# sbc-base.net
KiCad netlist of a schematic drawn in Altium Designer
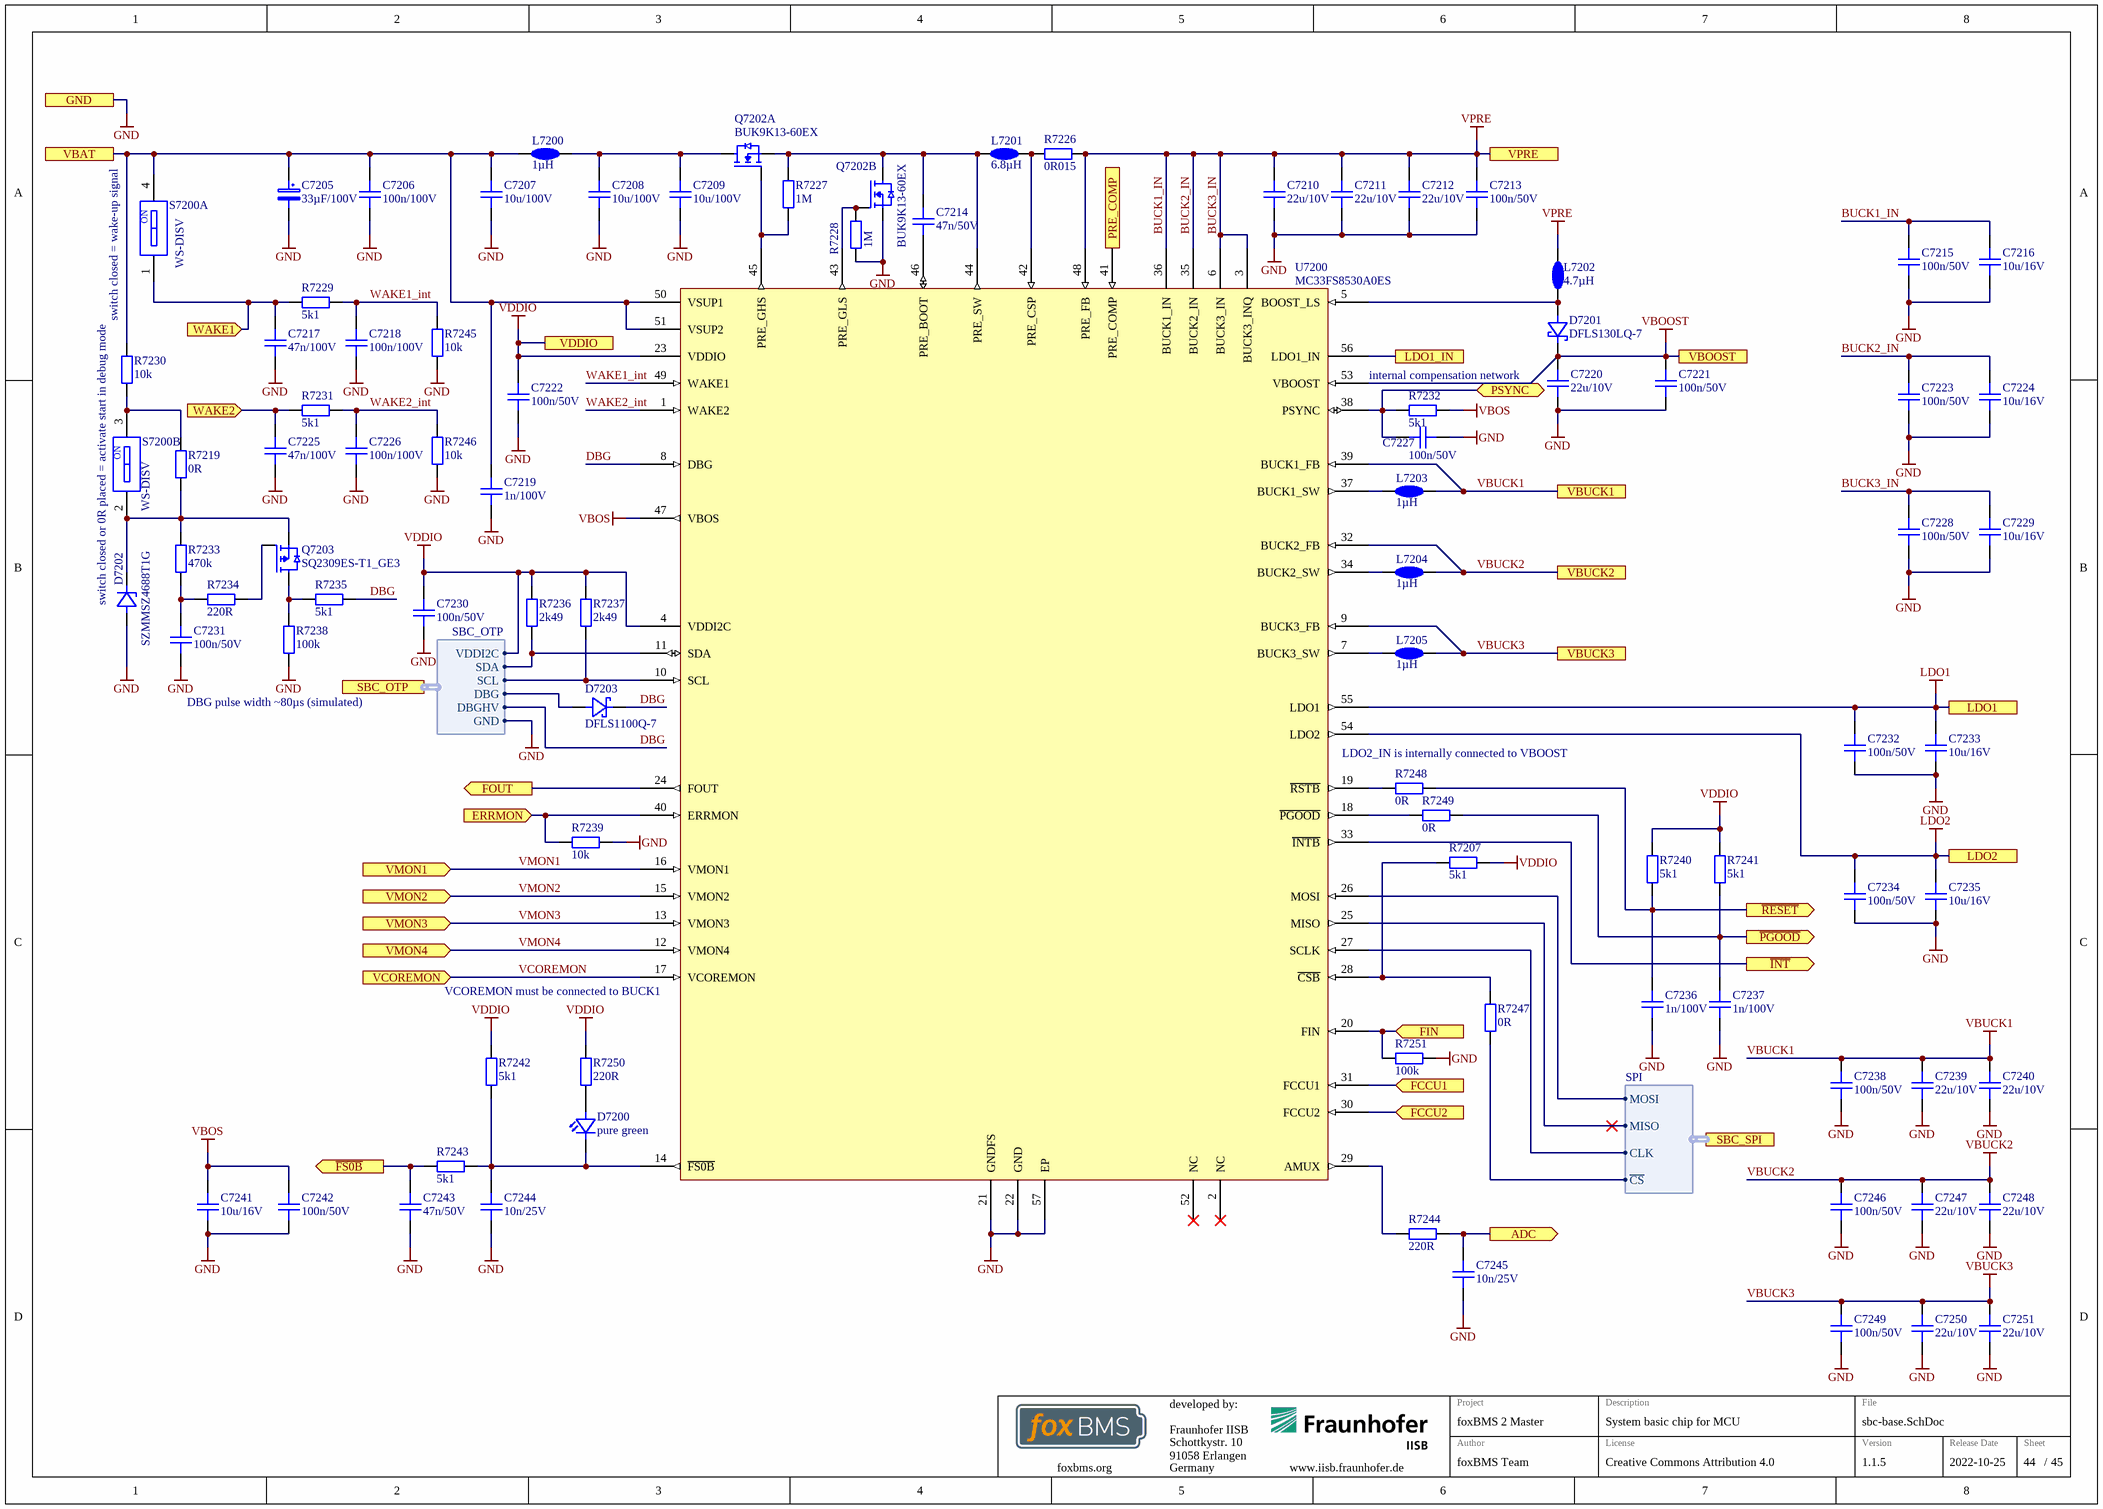
[diagram p0: sbc-base.SchDoc]

(export (version "E")
  (design (tool "Eeschema 10.0.6"))
  (components
    (comp (ref "C7205")
      (value "33µF/100V")
      (footprint "ELECTROLYTIC_CAP_PANASONIC_G")
      (description "SMD Electrolytic Capacitor")
      (fields (field (name "PART NUMBER") "EEE-TG2A330P") (field (name "TOLERANCE") "+-20%"))
      (libsource (lib "OE750") (part "C_Pol"))
    )
    (comp (ref "C7206")
      (value "100n/100V")
      (footprint "CAPC1608X08N")
      (description "MLCC")
      (fields (field (name "PART NUMBER") "gen_C_ceramic_100n_100V_X7R_0603"))
      (libsource (lib "OE750") (part "C"))
    )
    (comp (ref "C7207")
      (value "10u/100V")
      (footprint "CAPC5750X28N")
      (description "MLCC")
      (fields (field (name "PART NUMBER") "gen_C_ceramic_10u_100V_X7S_2220"))
      (libsource (lib "OE750") (part "C"))
    )
    (comp (ref "C7208")
      (value "10u/100V")
      (footprint "CAPC5750X28N")
      (description "MLCC")
      (fields (field (name "PART NUMBER") "gen_C_ceramic_10u_100V_X7S_2220"))
      (libsource (lib "OE750") (part "C"))
    )
    (comp (ref "C7209")
      (value "10u/100V")
      (footprint "CAPC5750X28N")
      (description "MLCC")
      (fields (field (name "PART NUMBER") "gen_C_ceramic_10u_100V_X7S_2220"))
      (libsource (lib "OE750") (part "C"))
    )
    (comp (ref "C7210")
      (value "22u/10V")
      (footprint "CAPC3216X18N")
      (description "MLCC")
      (fields (field (name "PART NUMBER") "gen_C_ceramic_22u_10V_X7R_1206"))
      (libsource (lib "OE750") (part "C"))
    )
    (comp (ref "C7211")
      (value "22u/10V")
      (footprint "CAPC3216X18N")
      (description "MLCC")
      (fields (field (name "PART NUMBER") "gen_C_ceramic_22u_10V_X7R_1206"))
      (libsource (lib "OE750") (part "C"))
    )
    (comp (ref "C7212")
      (value "22u/10V")
      (footprint "CAPC3216X18N")
      (description "MLCC")
      (fields (field (name "PART NUMBER") "gen_C_ceramic_22u_10V_X7R_1206"))
      (libsource (lib "OE750") (part "C"))
    )
    (comp (ref "C7213")
      (value "100n/50V")
      (footprint "CAPC1005X06N")
      (description "MLCC")
      (fields (field (name "PART NUMBER") "gen_C_ceramic_100n_50V_X7R_0402"))
      (libsource (lib "OE750") (part "C"))
    )
    (comp (ref "C7214")
      (value "47n/50V")
      (footprint "CAPC1005X06N")
      (description "MLCC")
      (fields (field (name "PART NUMBER") "gen_C_ceramic_47n_50V_X7R_0402"))
      (libsource (lib "OE750") (part "C"))
    )
    (comp (ref "C7215")
      (value "100n/50V")
      (footprint "CAPC1005X06N")
      (description "MLCC")
      (fields (field (name "PART NUMBER") "gen_C_ceramic_100n_50V_X7R_0402"))
      (libsource (lib "OE750") (part "C"))
    )
    (comp (ref "C7216")
      (value "10u/16V")
      (footprint "CAPC2012X14N")
      (description "MLCC")
      (fields (field (name "PART NUMBER") "gen_C_ceramic_10u_16V_X7R_0805"))
      (libsource (lib "OE750") (part "C"))
    )
    (comp (ref "C7217")
      (value "47n/100V")
      (footprint "CAPC1608X08N")
      (description "MLCC")
      (fields (field (name "PART NUMBER") "gen_C_ceramic_47n_100V_X7R_0603"))
      (libsource (lib "OE750") (part "C"))
    )
    (comp (ref "C7218")
      (value "100n/100V")
      (footprint "CAPC1608X08N")
      (description "MLCC")
      (fields (field (name "PART NUMBER") "gen_C_ceramic_100n_100V_X7R_0603"))
      (libsource (lib "OE750") (part "C"))
    )
    (comp (ref "C7219")
      (value "1n/100V")
      (footprint "CAPC1005X06N")
      (description "MLCC")
      (fields (field (name "PART NUMBER") "gen_C_ceramic_1n_100V_X7R_0402"))
      (libsource (lib "OE750") (part "C"))
    )
    (comp (ref "C7220")
      (value "22u/10V")
      (footprint "CAPC3216X18N")
      (description "MLCC")
      (fields (field (name "PART NUMBER") "gen_C_ceramic_22u_10V_X7R_1206"))
      (libsource (lib "OE750") (part "C"))
    )
    (comp (ref "C7221")
      (value "100n/50V")
      (footprint "CAPC1005X06N")
      (description "MLCC")
      (fields (field (name "PART NUMBER") "gen_C_ceramic_100n_50V_X7R_0402"))
      (libsource (lib "OE750") (part "C"))
    )
    (comp (ref "C7222")
      (value "100n/50V")
      (footprint "CAPC1005X06N")
      (description "MLCC")
      (fields (field (name "PART NUMBER") "gen_C_ceramic_100n_50V_X7R_0402"))
      (libsource (lib "OE750") (part "C"))
    )
    (comp (ref "C7223")
      (value "100n/50V")
      (footprint "CAPC1005X06N")
      (description "MLCC")
      (fields (field (name "PART NUMBER") "gen_C_ceramic_100n_50V_X7R_0402"))
      (libsource (lib "OE750") (part "C"))
    )
    (comp (ref "C7224")
      (value "10u/16V")
      (footprint "CAPC2012X14N")
      (description "MLCC")
      (fields (field (name "PART NUMBER") "gen_C_ceramic_10u_16V_X7R_0805"))
      (libsource (lib "OE750") (part "C"))
    )
    (comp (ref "C7225")
      (value "47n/100V")
      (footprint "CAPC1608X08N")
      (description "MLCC")
      (fields (field (name "PART NUMBER") "gen_C_ceramic_47n_100V_X7R_0603"))
      (libsource (lib "OE750") (part "C"))
    )
    (comp (ref "C7226")
      (value "100n/100V")
      (footprint "CAPC1608X08N")
      (description "MLCC")
      (fields (field (name "PART NUMBER") "gen_C_ceramic_100n_100V_X7R_0603"))
      (libsource (lib "OE750") (part "C"))
    )
    (comp (ref "C7227")
      (value "100n/50V")
      (footprint "CAPC1005X06N")
      (description "MLCC")
      (fields (field (name "PART NUMBER") "gen_C_ceramic_100n_50V_X7R_0402"))
      (libsource (lib "OE750") (part "C"))
    )
    (comp (ref "C7228")
      (value "100n/50V")
      (footprint "CAPC1005X06N")
      (description "MLCC")
      (fields (field (name "PART NUMBER") "gen_C_ceramic_100n_50V_X7R_0402"))
      (libsource (lib "OE750") (part "C"))
    )
    (comp (ref "C7229")
      (value "10u/16V")
      (footprint "CAPC2012X14N")
      (description "MLCC")
      (fields (field (name "PART NUMBER") "gen_C_ceramic_10u_16V_X7R_0805"))
      (libsource (lib "OE750") (part "C"))
    )
    (comp (ref "C7230")
      (value "100n/50V")
      (footprint "CAPC1005X06N")
      (description "MLCC")
      (fields (field (name "PART NUMBER") "gen_C_ceramic_100n_50V_X7R_0402"))
      (libsource (lib "OE750") (part "C"))
    )
    (comp (ref "C7231")
      (value "100n/50V")
      (footprint "CAPC1005X06N")
      (description "MLCC")
      (fields (field (name "PART NUMBER") "gen_C_ceramic_100n_50V_X7R_0402"))
      (libsource (lib "OE750") (part "C"))
    )
    (comp (ref "C7232")
      (value "100n/50V")
      (footprint "CAPC1005X06N")
      (description "MLCC")
      (fields (field (name "PART NUMBER") "gen_C_ceramic_100n_50V_X7R_0402"))
      (libsource (lib "OE750") (part "C"))
    )
    (comp (ref "C7233")
      (value "10u/16V")
      (footprint "CAPC2012X14N")
      (description "MLCC")
      (fields (field (name "PART NUMBER") "gen_C_ceramic_10u_16V_X7R_0805"))
      (libsource (lib "OE750") (part "C"))
    )
    (comp (ref "C7234")
      (value "100n/50V")
      (footprint "CAPC1005X06N")
      (description "MLCC")
      (fields (field (name "PART NUMBER") "gen_C_ceramic_100n_50V_X7R_0402"))
      (libsource (lib "OE750") (part "C"))
    )
    (comp (ref "C7235")
      (value "10u/16V")
      (footprint "CAPC2012X14N")
      (description "MLCC")
      (fields (field (name "PART NUMBER") "gen_C_ceramic_10u_16V_X7R_0805"))
      (libsource (lib "OE750") (part "C"))
    )
    (comp (ref "C7236")
      (value "1n/100V")
      (footprint "CAPC1005X06N")
      (description "MLCC")
      (fields (field (name "PART NUMBER") "gen_C_ceramic_1n_100V_X7R_0402"))
      (libsource (lib "OE750") (part "C"))
    )
    (comp (ref "C7237")
      (value "1n/100V")
      (footprint "CAPC1005X06N")
      (description "MLCC")
      (fields (field (name "PART NUMBER") "gen_C_ceramic_1n_100V_X7R_0402"))
      (libsource (lib "OE750") (part "C"))
    )
    (comp (ref "C7238")
      (value "100n/50V")
      (footprint "CAPC1005X06N")
      (description "MLCC")
      (fields (field (name "PART NUMBER") "gen_C_ceramic_100n_50V_X7R_0402"))
      (libsource (lib "OE750") (part "C"))
    )
    (comp (ref "C7239")
      (value "22u/10V")
      (footprint "CAPC3216X18N")
      (description "MLCC")
      (fields (field (name "PART NUMBER") "gen_C_ceramic_22u_10V_X7R_1206"))
      (libsource (lib "OE750") (part "C"))
    )
    (comp (ref "C7240")
      (value "22u/10V")
      (footprint "CAPC3216X18N")
      (description "MLCC")
      (fields (field (name "PART NUMBER") "gen_C_ceramic_22u_10V_X7R_1206"))
      (libsource (lib "OE750") (part "C"))
    )
    (comp (ref "C7241")
      (value "10u/16V")
      (footprint "CAPC2012X14N")
      (description "MLCC")
      (fields (field (name "PART NUMBER") "gen_C_ceramic_10u_16V_X7R_0805"))
      (libsource (lib "OE750") (part "C"))
    )
    (comp (ref "C7242")
      (value "100n/50V")
      (footprint "CAPC1005X06N")
      (description "MLCC")
      (fields (field (name "PART NUMBER") "gen_C_ceramic_100n_50V_X7R_0402"))
      (libsource (lib "OE750") (part "C"))
    )
    (comp (ref "C7243")
      (value "47n/50V")
      (footprint "CAPC1005X06N")
      (description "MLCC")
      (fields (field (name "PART NUMBER") "gen_C_ceramic_47n_50V_X7R_0402"))
      (libsource (lib "OE750") (part "C"))
    )
    (comp (ref "C7244")
      (value "10n/25V")
      (footprint "CAPC1005X06N")
      (description "MLCC")
      (fields (field (name "PART NUMBER") "gen_C_ceramic_10n_25V_X7R_0402"))
      (libsource (lib "OE750") (part "C"))
    )
    (comp (ref "C7245")
      (value "10n/25V")
      (footprint "CAPC1005X06N")
      (description "MLCC")
      (fields (field (name "PART NUMBER") "gen_C_ceramic_10n_25V_X7R_0402"))
      (libsource (lib "OE750") (part "C"))
    )
    (comp (ref "C7246")
      (value "100n/50V")
      (footprint "CAPC1005X06N")
      (description "MLCC")
      (fields (field (name "PART NUMBER") "gen_C_ceramic_100n_50V_X7R_0402"))
      (libsource (lib "OE750") (part "C"))
    )
    (comp (ref "C7247")
      (value "22u/10V")
      (footprint "CAPC3216X18N")
      (description "MLCC")
      (fields (field (name "PART NUMBER") "gen_C_ceramic_22u_10V_X7R_1206"))
      (libsource (lib "OE750") (part "C"))
    )
    (comp (ref "C7248")
      (value "22u/10V")
      (footprint "CAPC3216X18N")
      (description "MLCC")
      (fields (field (name "PART NUMBER") "gen_C_ceramic_22u_10V_X7R_1206"))
      (libsource (lib "OE750") (part "C"))
    )
    (comp (ref "C7249")
      (value "100n/50V")
      (footprint "CAPC1005X06N")
      (description "MLCC")
      (fields (field (name "PART NUMBER") "gen_C_ceramic_100n_50V_X7R_0402"))
      (libsource (lib "OE750") (part "C"))
    )
    (comp (ref "C7250")
      (value "22u/10V")
      (footprint "CAPC3216X18N")
      (description "MLCC")
      (fields (field (name "PART NUMBER") "gen_C_ceramic_22u_10V_X7R_1206"))
      (libsource (lib "OE750") (part "C"))
    )
    (comp (ref "C7251")
      (value "22u/10V")
      (footprint "CAPC3216X18N")
      (description "MLCC")
      (fields (field (name "PART NUMBER") "gen_C_ceramic_22u_10V_X7R_1206"))
      (libsource (lib "OE750") (part "C"))
    )
    (comp (ref "D7200")
      (value "pure green")
      (footprint "LEDC1608X07N")
      (description "TLMP1100-GS08")
      (fields (field (name "PART NUMBER") "LED_0603_pure_green_AECQ") (field (name "MANUFACTURER") "Vishay"))
      (libsource (lib "OE750") (part "D_LED"))
    )
    (comp (ref "D7201")
      (value "DFLS130LQ-7")
      (footprint "PowerDI123")
      (description "Schottky Diode")
      (fields (field (name "MANUFACTURER") "Diodes Inc."))
      (libsource (lib "OE750") (part "D_Schottky"))
    )
    (comp (ref "D7202")
      (value "SZMMSZ4688T1G")
      (footprint "SOD-123_CASE-425-04-ISSUE-G")
      (description "Zener Diode")
      (fields (field (name "MANUFACTURER") "ON Semiconductor"))
      (libsource (lib "OE750") (part "D_Zener"))
    )
    (comp (ref "D7203")
      (value "DFLS1100Q-7")
      (footprint "PowerDI123")
      (description "Schottky Diode")
      (fields (field (name "MANUFACTURER") "Diodes Inc."))
      (libsource (lib "OE750") (part "D_Schottky"))
    )
    (comp (ref "L7200")
      (value "1µH")
      (footprint "ASPIAIG-S4035")
      (description "Power Inductor")
      (fields (field (name "PART NUMBER") "ASPIAIG-S4035-1R0M-T") (field (name "MANUFACTURER") "Abracon LLC"))
      (libsource (lib "OE750") (part "L"))
    )
    (comp (ref "L7201")
      (value "6.8µH")
      (footprint "PA4342.XXXNLT_Footprint_2")
      (description "Power Inductor")
      (fields (field (name "PART NUMBER") "PA4342.682NLT") (field (name "MANUFACTURER") "Pulse"))
      (libsource (lib "OE750") (part "L"))
    )
    (comp (ref "L7202")
      (value "4.7µH")
      (footprint "ASPIAIG-S4035")
      (description "Power Inductor")
      (fields (field (name "PART NUMBER") "ASPIAIG-S4035-4R7M-T") (field (name "MANUFACTURER") "Abracon LLC"))
      (libsource (lib "OE750") (part "L"))
    )
    (comp (ref "L7203")
      (value "1µH")
      (footprint "TDK_TFM252012")
      (description "Power Inductor")
      (fields (field (name "PART NUMBER") "TFM252012ALMA1R0MTAA") (field (name "MANUFACTURER") "TDK"))
      (libsource (lib "OE750") (part "L"))
    )
    (comp (ref "L7204")
      (value "1µH")
      (footprint "TDK_TFM252012")
      (description "Power Inductor")
      (fields (field (name "PART NUMBER") "TFM252012ALMA1R0MTAA") (field (name "MANUFACTURER") "TDK"))
      (libsource (lib "OE750") (part "L"))
    )
    (comp (ref "L7205")
      (value "1µH")
      (footprint "TDK_TFM252012")
      (description "Power Inductor")
      (fields (field (name "PART NUMBER") "TFM252012ALMA1R0MTAA") (field (name "MANUFACTURER") "TDK"))
      (libsource (lib "OE750") (part "L"))
    )
    (comp (ref "Q7202")
      (value "BUK9K13-60EX")
      (footprint "NXP-SOT1205_N")
      (description "Dual N-channel 60 V, 12.5 mΩ logic level MOSFET")
      (fields (field (name "MANUFACTURER") "Nexperia"))
      (libsource (lib "OE750") (part "BUK9K35-60E"))
    )
    (comp (ref "Q7203")
      (value "SQ2309ES-T1_GE3")
      (footprint "SOT95P237X110-3N")
      (description "MOSFET-Transistor, p-channel, -1.7 A, -60 V")
      (fields (field (name "MANUFACTURER") "Vishay"))
      (libsource (lib "OE750") (part "PMOS"))
    )
    (comp (ref "R7207")
      (value "5k1")
      (footprint "RESC1005X04N")
      (description "SMD Resistor 5k1 0402")
      (fields (field (name "PART NUMBER") "gen_R_5k1_0402") (field (name "TOLERANCE") "1%"))
      (libsource (lib "OE750") (part "R"))
    )
    (comp (ref "R7219")
      (value "0R")
      (footprint "RESC1005X04N")
      (description "SMD Resistor 0R 0402")
      (fields (field (name "PART NUMBER") "gen_R_0R_0402") (field (name "POWER") "0.063W"))
      (libsource (lib "OE750") (part "R"))
    )
    (comp (ref "R7226")
      (value "0R015")
      (footprint "PANASONIC_ERJ-B1")
      (description "SMD Shunt Resistor 0R015")
      (fields (field (name "PART NUMBER") "ERJ-B1CFR015U") (field (name "TOLERANCE") "1%"))
      (libsource (lib "OE750") (part "R"))
    )
    (comp (ref "R7227")
      (value "1M")
      (footprint "RESC1005X04N")
      (description "SMD Resistor 1M 0402")
      (fields (field (name "PART NUMBER") "gen_R_1M_0402") (field (name "TOLERANCE") "1%"))
      (libsource (lib "OE750") (part "R"))
    )
    (comp (ref "R7228")
      (value "1M")
      (footprint "RESC1005X04N")
      (description "SMD Resistor 1M 0402")
      (fields (field (name "PART NUMBER") "gen_R_1M_0402") (field (name "TOLERANCE") "1%"))
      (libsource (lib "OE750") (part "R"))
    )
    (comp (ref "R7229")
      (value "5k1")
      (footprint "RESC1005X04N")
      (description "SMD Resistor 5k1 0402")
      (fields (field (name "PART NUMBER") "gen_R_5k1_0402") (field (name "TOLERANCE") "1%"))
      (libsource (lib "OE750") (part "R"))
    )
    (comp (ref "R7230")
      (value "10k")
      (footprint "RESC1005X04N")
      (description "SMD Resistor 10k 0402")
      (fields (field (name "PART NUMBER") "gen_R_10k_0402") (field (name "TOLERANCE") "1%"))
      (libsource (lib "OE750") (part "R"))
    )
    (comp (ref "R7231")
      (value "5k1")
      (footprint "RESC1005X04N")
      (description "SMD Resistor 5k1 0402")
      (fields (field (name "PART NUMBER") "gen_R_5k1_0402") (field (name "TOLERANCE") "1%"))
      (libsource (lib "OE750") (part "R"))
    )
    (comp (ref "R7232")
      (value "5k1")
      (footprint "RESC1005X04N")
      (description "SMD Resistor 5k1 0402")
      (fields (field (name "PART NUMBER") "gen_R_5k1_0402") (field (name "TOLERANCE") "1%"))
      (libsource (lib "OE750") (part "R"))
    )
    (comp (ref "R7233")
      (value "470k")
      (footprint "RESC1005X04N")
      (description "SMD Resistor 470k 0402")
      (fields (field (name "PART NUMBER") "gen_R_470k_0402") (field (name "TOLERANCE") "1%"))
      (libsource (lib "OE750") (part "R"))
    )
    (comp (ref "R7234")
      (value "220R")
      (footprint "RESC1005X04N")
      (description "SMD Resistor 220R 0402")
      (fields (field (name "PART NUMBER") "gen_R_220R_0402") (field (name "TOLERANCE") "1%"))
      (libsource (lib "OE750") (part "R"))
    )
    (comp (ref "R7235")
      (value "5k1")
      (footprint "RESC1005X04N")
      (description "SMD Resistor 5k1 0402")
      (fields (field (name "PART NUMBER") "gen_R_5k1_0402") (field (name "TOLERANCE") "1%"))
      (libsource (lib "OE750") (part "R"))
    )
    (comp (ref "R7236")
      (value "2k49")
      (footprint "RESC1005X04N")
      (description "SMD Resistor 2k49 0402")
      (fields (field (name "PART NUMBER") "gen_R_2k49_0402") (field (name "TOLERANCE") "1%"))
      (libsource (lib "OE750") (part "R"))
    )
    (comp (ref "R7237")
      (value "2k49")
      (footprint "RESC1005X04N")
      (description "SMD Resistor 2k49 0402")
      (fields (field (name "PART NUMBER") "gen_R_2k49_0402") (field (name "TOLERANCE") "1%"))
      (libsource (lib "OE750") (part "R"))
    )
    (comp (ref "R7238")
      (value "100k")
      (footprint "RESC1005X04N")
      (description "SMD Resistor 100k 0402")
      (fields (field (name "PART NUMBER") "gen_R_100k_0402") (field (name "TOLERANCE") "1%"))
      (libsource (lib "OE750") (part "R"))
    )
    (comp (ref "R7239")
      (value "10k")
      (footprint "RESC1005X04N")
      (description "SMD Resistor 10k 0402")
      (fields (field (name "PART NUMBER") "gen_R_10k_0402") (field (name "TOLERANCE") "1%"))
      (libsource (lib "OE750") (part "R"))
    )
    (comp (ref "R7240")
      (value "5k1")
      (footprint "RESC1005X04N")
      (description "SMD Resistor 5k1 0402")
      (fields (field (name "PART NUMBER") "gen_R_5k1_0402") (field (name "TOLERANCE") "1%"))
      (libsource (lib "OE750") (part "R"))
    )
    (comp (ref "R7241")
      (value "5k1")
      (footprint "RESC1005X04N")
      (description "SMD Resistor 5k1 0402")
      (fields (field (name "PART NUMBER") "gen_R_5k1_0402") (field (name "TOLERANCE") "1%"))
      (libsource (lib "OE750") (part "R"))
    )
    (comp (ref "R7242")
      (value "5k1")
      (footprint "RESC1005X04N")
      (description "SMD Resistor 5k1 0402")
      (fields (field (name "PART NUMBER") "gen_R_5k1_0402") (field (name "TOLERANCE") "1%"))
      (libsource (lib "OE750") (part "R"))
    )
    (comp (ref "R7243")
      (value "5k1")
      (footprint "RESC1005X04N")
      (description "SMD Resistor 5k1 0402")
      (fields (field (name "PART NUMBER") "gen_R_5k1_0402") (field (name "TOLERANCE") "1%"))
      (libsource (lib "OE750") (part "R"))
    )
    (comp (ref "R7244")
      (value "220R")
      (footprint "RESC1005X04N")
      (description "SMD Resistor 220R 0402")
      (fields (field (name "PART NUMBER") "gen_R_220R_0402") (field (name "TOLERANCE") "1%"))
      (libsource (lib "OE750") (part "R"))
    )
    (comp (ref "R7245")
      (value "10k")
      (footprint "RESC1005X04N")
      (description "SMD Resistor 10k 0402")
      (fields (field (name "PART NUMBER") "gen_R_10k_0402") (field (name "TOLERANCE") "1%"))
      (libsource (lib "OE750") (part "R"))
    )
    (comp (ref "R7246")
      (value "10k")
      (footprint "RESC1005X04N")
      (description "SMD Resistor 10k 0402")
      (fields (field (name "PART NUMBER") "gen_R_10k_0402") (field (name "TOLERANCE") "1%"))
      (libsource (lib "OE750") (part "R"))
    )
    (comp (ref "R7247")
      (value "0R")
      (footprint "RESC1005X04N")
      (description "SMD Resistor 0R 0402")
      (fields (field (name "PART NUMBER") "gen_R_0R_0402") (field (name "POWER") "0.063W"))
      (libsource (lib "OE750") (part "R"))
    )
    (comp (ref "R7248")
      (value "0R")
      (footprint "RESC1005X04N")
      (description "SMD Resistor 0R 0402")
      (fields (field (name "PART NUMBER") "gen_R_0R_0402") (field (name "POWER") "0.063W"))
      (libsource (lib "OE750") (part "R"))
    )
    (comp (ref "R7249")
      (value "0R")
      (footprint "RESC1005X04N")
      (description "SMD Resistor 0R 0402")
      (fields (field (name "PART NUMBER") "gen_R_0R_0402") (field (name "POWER") "0.063W"))
      (libsource (lib "OE750") (part "R"))
    )
    (comp (ref "R7250")
      (value "220R")
      (footprint "RESC1005X04N")
      (description "SMD Resistor 220R 0402")
      (fields (field (name "PART NUMBER") "gen_R_220R_0402") (field (name "TOLERANCE") "1%"))
      (libsource (lib "OE750") (part "R"))
    )
    (comp (ref "R7251")
      (value "100k")
      (footprint "RESC1005X04N")
      (description "SMD Resistor 100k 0402")
      (fields (field (name "PART NUMBER") "gen_R_100k_0402") (field (name "TOLERANCE") "1%"))
      (libsource (lib "OE750") (part "R"))
    )
    (comp (ref "S7200")
      (value "WS-DISV")
      (footprint "WE_416131160802")
      (description "WS-DISV Small Compact SMT DipSwitch")
      (fields (field (name "PART NUMBER") "WE_416131160802") (field (name "MANUFACTURER") "Würth Elektronik"))
      (libsource (lib "OE750") (part "WE_416131160802"))
    )
    (comp (ref "U7200")
      (value "MC33FS8530A0ES")
      (footprint "MC33FS8530A0ES")
      (description "Fail-safe system basis chip with multiple SMPS and LDO")
      (fields (field (name "MANUFACTURER") "NXP"))
      (libsource (lib "OE750") (part "MC33FS8530A0ES"))
    )
  )
  (nets
    (net (code "3") (name "/ADC") (class "Default")
      (node (ref "C7245") (pin "2") (pinfunction "2_2") (pintype "passive"))
      (node (ref "R7244") (pin "2") (pinfunction "2_2") (pintype "passive"))
    )
    (net (code "4") (name "/CLK") (class "Default")
      (node (ref "U7200") (pin "27") (pinfunction "SCLK_27") (pintype "input"))
    )
    (net (code "5") (name "/DBG") (class "Default")
      (node (ref "D7203") (pin "1") (pinfunction "K_1") (pintype "passive"))
      (node (ref "R7235") (pin "1") (pinfunction "1_1") (pintype "passive"))
      (node (ref "U7200") (pin "8") (pinfunction "DBG_8") (pintype "input"))
    )
    (net (code "6") (name "/ERRMON") (class "Default")
      (node (ref "R7239") (pin "2") (pinfunction "2_2") (pintype "passive"))
      (node (ref "U7200") (pin "40") (pinfunction "ERRMON_40") (pintype "input"))
    )
    (net (code "7") (name "/FCCU1") (class "Default")
      (node (ref "U7200") (pin "31") (pinfunction "FCCU1_31") (pintype "input"))
    )
    (net (code "8") (name "/FCCU2") (class "Default")
      (node (ref "U7200") (pin "30") (pinfunction "FCCU2_30") (pintype "input"))
    )
    (net (code "9") (name "/FIN") (class "Default")
      (node (ref "R7251") (pin "1") (pinfunction "1_1") (pintype "passive"))
      (node (ref "U7200") (pin "20") (pinfunction "FIN_20") (pintype "input"))
    )
    (net (code "10") (name "/FOUT") (class "Default")
      (node (ref "U7200") (pin "24") (pinfunction "FOUT_24") (pintype "output"))
    )
    (net (code "11") (name "/FS0B") (class "Default")
      (node (ref "C7243") (pin "2") (pinfunction "2_2") (pintype "passive"))
      (node (ref "R7243") (pin "2") (pinfunction "2_2") (pintype "passive"))
    )
    (net (code "12") (name "/INT") (class "Default")
      (node (ref "U7200") (pin "33") (pinfunction "INTB_33") (pintype "output"))
    )
    (net (code "13") (name "/LDO1_IN") (class "Default")
      (node (ref "U7200") (pin "56") (pinfunction "LDO1_IN_56") (pintype "power_in"))
    )
    (net (code "14") (name "/MISO") (class "Default")
      (node (ref "U7200") (pin "25") (pinfunction "MISO_25") (pintype "output"))
    )
    (net (code "15") (name "/MOSI") (class "Default")
      (node (ref "U7200") (pin "26") (pinfunction "MOSI_26") (pintype "input"))
    )
    (net (code "16") (name "/PGOOD") (class "Default")
      (node (ref "C7237") (pin "2") (pinfunction "2_2") (pintype "passive"))
      (node (ref "R7241") (pin "1") (pinfunction "1_1") (pintype "passive"))
      (node (ref "R7249") (pin "2") (pinfunction "2_2") (pintype "passive"))
    )
    (net (code "17") (name "/PRE_COMP") (class "Default")
      (node (ref "U7200") (pin "41") (pinfunction "PRE_COMP_41") (pintype "input"))
    )
    (net (code "18") (name "/PSYNC") (class "Default")
      (node (ref "C7227") (pin "2") (pinfunction "2_2") (pintype "passive"))
      (node (ref "R7232") (pin "1") (pinfunction "1_1") (pintype "passive"))
      (node (ref "U7200") (pin "38") (pinfunction "PSYNC_38") (pintype "bidirectional"))
    )
    (net (code "19") (name "/RESET") (class "Default")
      (node (ref "C7236") (pin "2") (pinfunction "2_2") (pintype "passive"))
      (node (ref "R7240") (pin "1") (pinfunction "1_1") (pintype "passive"))
      (node (ref "R7248") (pin "1") (pinfunction "1_1") (pintype "passive"))
    )
    (net (code "20") (name "/SCL") (class "Default")
      (node (ref "R7237") (pin "1") (pinfunction "1_1") (pintype "passive"))
      (node (ref "U7200") (pin "10") (pinfunction "SCL_10") (pintype "input"))
    )
    (net (code "21") (name "/SDA") (class "Default")
      (node (ref "R7236") (pin "1") (pinfunction "1_1") (pintype "passive"))
      (node (ref "U7200") (pin "11") (pinfunction "SDA_11") (pintype "bidirectional"))
    )
    (net (code "22") (name "/VBAT") (class "Default")
      (node (ref "C7205") (pin "1") (pinfunction "1_1") (pintype "passive"))
      (node (ref "C7206") (pin "2") (pinfunction "2_2") (pintype "passive"))
      (node (ref "C7207") (pin "2") (pinfunction "2_2") (pintype "passive"))
      (node (ref "C7219") (pin "2") (pinfunction "2_2") (pintype "passive"))
      (node (ref "L7200") (pin "1") (pinfunction "1_1") (pintype "passive"))
      (node (ref "R7230") (pin "2") (pinfunction "2_2") (pintype "passive"))
      (node (ref "S7200") (pin "4") (pinfunction "4_4") (pintype "passive"))
      (node (ref "U7200") (pin "50") (pinfunction "VSUP1_50") (pintype "power_in"))
      (node (ref "U7200") (pin "51") (pinfunction "VSUP2_51") (pintype "power_in"))
    )
    (net (code "23") (name "/VCOREMON") (class "Default")
      (node (ref "U7200") (pin "17") (pinfunction "VCOREMON_17") (pintype "input"))
    )
    (net (code "24") (name "/VMON1") (class "Default")
      (node (ref "U7200") (pin "16") (pinfunction "VMON1_16") (pintype "input"))
    )
    (net (code "25") (name "/VMON2") (class "Default")
      (node (ref "U7200") (pin "15") (pinfunction "VMON2_15") (pintype "input"))
    )
    (net (code "26") (name "/VMON3") (class "Default")
      (node (ref "U7200") (pin "13") (pinfunction "VMON3_13") (pintype "input"))
    )
    (net (code "27") (name "/VMON4") (class "Default")
      (node (ref "U7200") (pin "12") (pinfunction "VMON4_12") (pintype "input"))
    )
    (net (code "28") (name "/WAKE1") (class "Default")
      (node (ref "C7217") (pin "2") (pinfunction "2_2") (pintype "passive"))
      (node (ref "R7229") (pin "2") (pinfunction "2_2") (pintype "passive"))
      (node (ref "S7200") (pin "1") (pinfunction "1_1") (pintype "passive"))
    )
    (net (code "29") (name "/WAKE1_int") (class "Default")
      (node (ref "C7218") (pin "2") (pinfunction "2_2") (pintype "passive"))
      (node (ref "R7229") (pin "1") (pinfunction "1_1") (pintype "passive"))
      (node (ref "R7245") (pin "1") (pinfunction "1_1") (pintype "passive"))
      (node (ref "U7200") (pin "49") (pinfunction "WAKE1_49") (pintype "input"))
    )
    (net (code "30") (name "/WAKE2") (class "Default")
      (node (ref "C7225") (pin "2") (pinfunction "2_2") (pintype "passive"))
      (node (ref "R7231") (pin "2") (pinfunction "2_2") (pintype "passive"))
    )
    (net (code "31") (name "/WAKE2_int") (class "Default")
      (node (ref "C7226") (pin "2") (pinfunction "2_2") (pintype "passive"))
      (node (ref "R7231") (pin "1") (pinfunction "1_1") (pintype "passive"))
      (node (ref "R7246") (pin "1") (pinfunction "1_1") (pintype "passive"))
      (node (ref "U7200") (pin "1") (pinfunction "WAKE2_1") (pintype "input"))
    )
    (net (code "34") (name "/~{CS}") (class "Default")
      (node (ref "R7247") (pin "1") (pinfunction "1_1") (pintype "passive"))
    )
    (net (code "35") (name "GND") (class "Default")
      (node (ref "C7205") (pin "2") (pinfunction "2_2") (pintype "passive"))
      (node (ref "C7206") (pin "1") (pinfunction "1_1") (pintype "passive"))
      (node (ref "C7207") (pin "1") (pinfunction "1_1") (pintype "passive"))
      (node (ref "C7208") (pin "1") (pinfunction "1_1") (pintype "passive"))
      (node (ref "C7209") (pin "1") (pinfunction "1_1") (pintype "passive"))
      (node (ref "C7210") (pin "1") (pinfunction "1_1") (pintype "passive"))
      (node (ref "C7211") (pin "1") (pinfunction "1_1") (pintype "passive"))
      (node (ref "C7212") (pin "1") (pinfunction "1_1") (pintype "passive"))
      (node (ref "C7213") (pin "1") (pinfunction "1_1") (pintype "passive"))
      (node (ref "C7215") (pin "1") (pinfunction "1_1") (pintype "passive"))
      (node (ref "C7216") (pin "1") (pinfunction "1_1") (pintype "passive"))
      (node (ref "C7217") (pin "1") (pinfunction "1_1") (pintype "passive"))
      (node (ref "C7218") (pin "1") (pinfunction "1_1") (pintype "passive"))
      (node (ref "C7219") (pin "1") (pinfunction "1_1") (pintype "passive"))
      (node (ref "C7220") (pin "1") (pinfunction "1_1") (pintype "passive"))
      (node (ref "C7221") (pin "1") (pinfunction "1_1") (pintype "passive"))
      (node (ref "C7222") (pin "1") (pinfunction "1_1") (pintype "passive"))
      (node (ref "C7223") (pin "1") (pinfunction "1_1") (pintype "passive"))
      (node (ref "C7224") (pin "1") (pinfunction "1_1") (pintype "passive"))
      (node (ref "C7225") (pin "1") (pinfunction "1_1") (pintype "passive"))
      (node (ref "C7226") (pin "1") (pinfunction "1_1") (pintype "passive"))
      (node (ref "C7227") (pin "1") (pinfunction "1_1") (pintype "passive"))
      (node (ref "C7228") (pin "1") (pinfunction "1_1") (pintype "passive"))
      (node (ref "C7229") (pin "1") (pinfunction "1_1") (pintype "passive"))
      (node (ref "C7230") (pin "1") (pinfunction "1_1") (pintype "passive"))
      (node (ref "C7231") (pin "1") (pinfunction "1_1") (pintype "passive"))
      (node (ref "C7232") (pin "1") (pinfunction "1_1") (pintype "passive"))
      (node (ref "C7233") (pin "1") (pinfunction "1_1") (pintype "passive"))
      (node (ref "C7234") (pin "1") (pinfunction "1_1") (pintype "passive"))
      (node (ref "C7235") (pin "1") (pinfunction "1_1") (pintype "passive"))
      (node (ref "C7236") (pin "1") (pinfunction "1_1") (pintype "passive"))
      (node (ref "C7237") (pin "1") (pinfunction "1_1") (pintype "passive"))
      (node (ref "C7238") (pin "1") (pinfunction "1_1") (pintype "passive"))
      (node (ref "C7239") (pin "1") (pinfunction "1_1") (pintype "passive"))
      (node (ref "C7240") (pin "1") (pinfunction "1_1") (pintype "passive"))
      (node (ref "C7241") (pin "1") (pinfunction "1_1") (pintype "passive"))
      (node (ref "C7242") (pin "1") (pinfunction "1_1") (pintype "passive"))
      (node (ref "C7243") (pin "1") (pinfunction "1_1") (pintype "passive"))
      (node (ref "C7244") (pin "1") (pinfunction "1_1") (pintype "passive"))
      (node (ref "C7245") (pin "1") (pinfunction "1_1") (pintype "passive"))
      (node (ref "C7246") (pin "1") (pinfunction "1_1") (pintype "passive"))
      (node (ref "C7247") (pin "1") (pinfunction "1_1") (pintype "passive"))
      (node (ref "C7248") (pin "1") (pinfunction "1_1") (pintype "passive"))
      (node (ref "C7249") (pin "1") (pinfunction "1_1") (pintype "passive"))
      (node (ref "C7250") (pin "1") (pinfunction "1_1") (pintype "passive"))
      (node (ref "C7251") (pin "1") (pinfunction "1_1") (pintype "passive"))
      (node (ref "D7202") (pin "2") (pinfunction "A_2") (pintype "passive"))
      (node (ref "Q7202") (pin "3") (pinfunction "S_3") (pintype "passive"))
      (node (ref "R7228") (pin "1") (pinfunction "1_1") (pintype "passive"))
      (node (ref "R7238") (pin "1") (pinfunction "1_1") (pintype "passive"))
      (node (ref "R7239") (pin "1") (pinfunction "1_1") (pintype "passive"))
      (node (ref "R7245") (pin "2") (pinfunction "2_2") (pintype "passive"))
      (node (ref "R7246") (pin "2") (pinfunction "2_2") (pintype "passive"))
      (node (ref "R7251") (pin "2") (pinfunction "2_2") (pintype "passive"))
      (node (ref "U7200") (pin "21") (pinfunction "GNDFS_21") (pintype "power_in"))
      (node (ref "U7200") (pin "22") (pinfunction "GND_22") (pintype "power_in"))
      (node (ref "U7200") (pin "57") (pinfunction "EP_57") (pintype "power_in"))
    )
    (net (code "36") (name "LDO1") (class "Default")
      (node (ref "C7232") (pin "2") (pinfunction "2_2") (pintype "passive"))
      (node (ref "C7233") (pin "2") (pinfunction "2_2") (pintype "passive"))
      (node (ref "U7200") (pin "55") (pinfunction "LDO1_55") (pintype "output"))
    )
    (net (code "37") (name "LDO2") (class "Default")
      (node (ref "C7234") (pin "2") (pinfunction "2_2") (pintype "passive"))
      (node (ref "C7235") (pin "2") (pinfunction "2_2") (pintype "passive"))
      (node (ref "U7200") (pin "54") (pinfunction "LDO2_54") (pintype "output"))
    )
    (net (code "38") (name "Net-(C7231-Pad2)") (class "Default")
      (node (ref "C7231") (pin "2") (pinfunction "2_2") (pintype "passive"))
      (node (ref "R7233") (pin "1") (pinfunction "1_1") (pintype "passive"))
      (node (ref "R7234") (pin "1") (pinfunction "1_1") (pintype "passive"))
    )
    (net (code "39") (name "Net-(D7200-A)") (class "Default")
      (node (ref "D7200") (pin "2") (pinfunction "A_2") (pintype "passive"))
      (node (ref "R7250") (pin "1") (pinfunction "1_1") (pintype "passive"))
    )
    (net (code "40") (name "Net-(D7200-C)") (class "Default")
      (node (ref "C7244") (pin "2") (pinfunction "2_2") (pintype "passive"))
      (node (ref "D7200") (pin "1") (pinfunction "C_1") (pintype "passive"))
      (node (ref "R7242") (pin "1") (pinfunction "1_1") (pintype "passive"))
      (node (ref "R7243") (pin "1") (pinfunction "1_1") (pintype "passive"))
      (node (ref "U7200") (pin "14") (pinfunction "FS0B_14") (pintype "output"))
    )
    (net (code "41") (name "Net-(D7201-A)") (class "Default")
      (node (ref "D7201") (pin "2") (pinfunction "A_2") (pintype "passive"))
      (node (ref "L7202") (pin "1") (pinfunction "1_1") (pintype "passive"))
      (node (ref "U7200") (pin "5") (pinfunction "BOOST_LS_5") (pintype "input"))
    )
    (net (code "42") (name "Net-(D7202-K)") (class "Default")
      (node (ref "D7202") (pin "1") (pinfunction "K_1") (pintype "passive"))
      (node (ref "Q7203") (pin "S") (pinfunction "S_S") (pintype "passive"))
      (node (ref "R7219") (pin "1") (pinfunction "1_1") (pintype "passive"))
      (node (ref "R7233") (pin "2") (pinfunction "2_2") (pintype "passive"))
      (node (ref "S7200") (pin "2") (pinfunction "2_2") (pintype "passive"))
    )
    (net (code "43") (name "Net-(Q7202A-D)") (class "Default")
      (node (ref "C7208") (pin "2") (pinfunction "2_2") (pintype "passive"))
      (node (ref "C7209") (pin "2") (pinfunction "2_2") (pintype "passive"))
      (node (ref "L7200") (pin "2") (pinfunction "2_2") (pintype "passive"))
      (node (ref "Q7202") (pin "7") (pinfunction "D_7") (pintype "passive"))
    )
    (net (code "44") (name "Net-(Q7202A-G)") (class "Default")
      (node (ref "Q7202") (pin "2") (pinfunction "G_2") (pintype "passive"))
      (node (ref "R7227") (pin "1") (pinfunction "1_1") (pintype "passive"))
      (node (ref "U7200") (pin "45") (pinfunction "PRE_GHS_45") (pintype "output"))
    )
    (net (code "45") (name "Net-(Q7202A-S)") (class "Default")
      (node (ref "C7214") (pin "2") (pinfunction "2_2") (pintype "passive"))
      (node (ref "L7201") (pin "1") (pinfunction "1_1") (pintype "passive"))
      (node (ref "Q7202") (pin "1") (pinfunction "S_1") (pintype "passive"))
      (node (ref "Q7202") (pin "5") (pinfunction "D_5") (pintype "passive"))
      (node (ref "R7227") (pin "2") (pinfunction "2_2") (pintype "passive"))
      (node (ref "U7200") (pin "44") (pinfunction "PRE_SW_44") (pintype "output"))
    )
    (net (code "46") (name "Net-(Q7202B-G)") (class "Default")
      (node (ref "Q7202") (pin "4") (pinfunction "G_4") (pintype "passive"))
      (node (ref "R7228") (pin "2") (pinfunction "2_2") (pintype "passive"))
      (node (ref "U7200") (pin "43") (pinfunction "PRE_GLS_43") (pintype "output"))
    )
    (net (code "47") (name "Net-(Q7203-PadD)") (class "Default")
      (node (ref "Q7203") (pin "D") (pinfunction "D_D") (pintype "passive"))
      (node (ref "R7235") (pin "2") (pinfunction "2_2") (pintype "passive"))
      (node (ref "R7238") (pin "2") (pinfunction "2_2") (pintype "passive"))
    )
    (net (code "48") (name "Net-(Q7203-PadG)") (class "Default")
      (node (ref "Q7203") (pin "G") (pinfunction "G_G") (pintype "passive"))
      (node (ref "R7234") (pin "2") (pinfunction "2_2") (pintype "passive"))
    )
    (net (code "49") (name "Net-(R7219-Pad2)") (class "Default")
      (node (ref "R7219") (pin "2") (pinfunction "2_2") (pintype "passive"))
      (node (ref "R7230") (pin "1") (pinfunction "1_1") (pintype "passive"))
      (node (ref "S7200") (pin "3") (pinfunction "3_3") (pintype "passive"))
    )
    (net (code "50") (name "Net-(U7200-AMUX)") (class "Default")
      (node (ref "R7244") (pin "1") (pinfunction "1_1") (pintype "passive"))
      (node (ref "U7200") (pin "29") (pinfunction "AMUX_29") (pintype "output"))
    )
    (net (code "51") (name "Net-(U7200-BUCK1_SW)") (class "Default")
      (node (ref "L7203") (pin "1") (pinfunction "1_1") (pintype "passive"))
      (node (ref "U7200") (pin "37") (pinfunction "BUCK1_SW_37") (pintype "output"))
    )
    (net (code "52") (name "Net-(U7200-BUCK2_SW)") (class "Default")
      (node (ref "L7204") (pin "1") (pinfunction "1_1") (pintype "passive"))
      (node (ref "U7200") (pin "34") (pinfunction "BUCK2_SW_34") (pintype "output"))
    )
    (net (code "53") (name "Net-(U7200-BUCK3_SW)") (class "Default")
      (node (ref "L7205") (pin "1") (pinfunction "1_1") (pintype "passive"))
      (node (ref "U7200") (pin "7") (pinfunction "BUCK3_SW_7") (pintype "output"))
    )
    (net (code "54") (name "Net-(U7200-CSB)") (class "Default")
      (node (ref "R7207") (pin "2") (pinfunction "2_2") (pintype "passive"))
      (node (ref "R7247") (pin "2") (pinfunction "2_2") (pintype "passive"))
      (node (ref "U7200") (pin "28") (pinfunction "CSB_28") (pintype "input"))
    )
    (net (code "55") (name "Net-(U7200-PGOOD)") (class "Default")
      (node (ref "R7249") (pin "1") (pinfunction "1_1") (pintype "passive"))
      (node (ref "U7200") (pin "18") (pinfunction "PGOOD_18") (pintype "output"))
    )
    (net (code "56") (name "Net-(U7200-PRE_BOOT)") (class "Default")
      (node (ref "C7214") (pin "1") (pinfunction "1_1") (pintype "passive"))
      (node (ref "U7200") (pin "46") (pinfunction "PRE_BOOT_46") (pintype "bidirectional"))
    )
    (net (code "57") (name "Net-(U7200-PRE_CSP)") (class "Default")
      (node (ref "L7201") (pin "2") (pinfunction "2_2") (pintype "passive"))
      (node (ref "R7226") (pin "1") (pinfunction "1_1") (pintype "passive"))
      (node (ref "U7200") (pin "42") (pinfunction "PRE_CSP_42") (pintype "input"))
    )
    (net (code "58") (name "Net-(U7200-RSTB)") (class "Default")
      (node (ref "R7248") (pin "2") (pinfunction "2_2") (pintype "passive"))
      (node (ref "U7200") (pin "19") (pinfunction "RSTB_19") (pintype "output"))
    )
    (net (code "59") (name "VBOOST") (class "Default")
      (node (ref "C7220") (pin "2") (pinfunction "2_2") (pintype "passive"))
      (node (ref "C7221") (pin "2") (pinfunction "2_2") (pintype "passive"))
      (node (ref "D7201") (pin "1") (pinfunction "K_1") (pintype "passive"))
      (node (ref "U7200") (pin "53") (pinfunction "VBOOST_53") (pintype "input"))
    )
    (net (code "60") (name "VBOS") (class "Default")
      (node (ref "C7241") (pin "2") (pinfunction "2_2") (pintype "passive"))
      (node (ref "C7242") (pin "2") (pinfunction "2_2") (pintype "passive"))
      (node (ref "R7232") (pin "2") (pinfunction "2_2") (pintype "passive"))
      (node (ref "U7200") (pin "47") (pinfunction "VBOS_47") (pintype "output"))
    )
    (net (code "61") (name "VBUCK1") (class "Default")
      (node (ref "C7238") (pin "2") (pinfunction "2_2") (pintype "passive"))
      (node (ref "C7239") (pin "2") (pinfunction "2_2") (pintype "passive"))
      (node (ref "C7240") (pin "2") (pinfunction "2_2") (pintype "passive"))
      (node (ref "L7203") (pin "2") (pinfunction "2_2") (pintype "passive"))
      (node (ref "U7200") (pin "39") (pinfunction "BUCK1_FB_39") (pintype "input"))
    )
    (net (code "62") (name "VBUCK2") (class "Default")
      (node (ref "C7246") (pin "2") (pinfunction "2_2") (pintype "passive"))
      (node (ref "C7247") (pin "2") (pinfunction "2_2") (pintype "passive"))
      (node (ref "C7248") (pin "2") (pinfunction "2_2") (pintype "passive"))
      (node (ref "L7204") (pin "2") (pinfunction "2_2") (pintype "passive"))
      (node (ref "U7200") (pin "32") (pinfunction "BUCK2_FB_32") (pintype "input"))
    )
    (net (code "63") (name "VBUCK3") (class "Default")
      (node (ref "C7249") (pin "2") (pinfunction "2_2") (pintype "passive"))
      (node (ref "C7250") (pin "2") (pinfunction "2_2") (pintype "passive"))
      (node (ref "C7251") (pin "2") (pinfunction "2_2") (pintype "passive"))
      (node (ref "L7205") (pin "2") (pinfunction "2_2") (pintype "passive"))
      (node (ref "U7200") (pin "9") (pinfunction "BUCK3_FB_9") (pintype "input"))
    )
    (net (code "64") (name "VDDIO") (class "Default")
      (node (ref "C7222") (pin "2") (pinfunction "2_2") (pintype "passive"))
      (node (ref "C7230") (pin "2") (pinfunction "2_2") (pintype "passive"))
      (node (ref "R7207") (pin "1") (pinfunction "1_1") (pintype "passive"))
      (node (ref "R7236") (pin "2") (pinfunction "2_2") (pintype "passive"))
      (node (ref "R7237") (pin "2") (pinfunction "2_2") (pintype "passive"))
      (node (ref "R7240") (pin "2") (pinfunction "2_2") (pintype "passive"))
      (node (ref "R7241") (pin "2") (pinfunction "2_2") (pintype "passive"))
      (node (ref "R7242") (pin "2") (pinfunction "2_2") (pintype "passive"))
      (node (ref "R7250") (pin "2") (pinfunction "2_2") (pintype "passive"))
      (node (ref "U7200") (pin "23") (pinfunction "VDDIO_23") (pintype "power_in"))
      (node (ref "U7200") (pin "4") (pinfunction "VDDI2C_4") (pintype "power_in"))
    )
    (net (code "65") (name "VPRE") (class "Default")
      (node (ref "C7210") (pin "2") (pinfunction "2_2") (pintype "passive"))
      (node (ref "C7211") (pin "2") (pinfunction "2_2") (pintype "passive"))
      (node (ref "C7212") (pin "2") (pinfunction "2_2") (pintype "passive"))
      (node (ref "C7213") (pin "2") (pinfunction "2_2") (pintype "passive"))
      (node (ref "C7215") (pin "2") (pinfunction "2_2") (pintype "passive"))
      (node (ref "C7216") (pin "2") (pinfunction "2_2") (pintype "passive"))
      (node (ref "C7223") (pin "2") (pinfunction "2_2") (pintype "passive"))
      (node (ref "C7224") (pin "2") (pinfunction "2_2") (pintype "passive"))
      (node (ref "C7228") (pin "2") (pinfunction "2_2") (pintype "passive"))
      (node (ref "C7229") (pin "2") (pinfunction "2_2") (pintype "passive"))
      (node (ref "L7202") (pin "2") (pinfunction "2_2") (pintype "passive"))
      (node (ref "R7226") (pin "2") (pinfunction "2_2") (pintype "passive"))
      (node (ref "U7200") (pin "3") (pinfunction "BUCK3_INQ_3") (pintype "power_in"))
      (node (ref "U7200") (pin "35") (pinfunction "BUCK2_IN_35") (pintype "power_in"))
      (node (ref "U7200") (pin "36") (pinfunction "BUCK1_IN_36") (pintype "power_in"))
      (node (ref "U7200") (pin "48") (pinfunction "PRE_FB_48") (pintype "input"))
      (node (ref "U7200") (pin "6") (pinfunction "BUCK3_IN_6") (pintype "power_in"))
    )
    (net (code "66") (name "unconnected-(D7203-A-Pad2)") (class "Default")
      (node (ref "D7203") (pin "2") (pinfunction "A_2") (pintype "passive"))
    )
    (net (code "67") (name "unconnected-(U7200-NC-Pad2)") (class "Default")
      (node (ref "U7200") (pin "2") (pinfunction "NC_2") (pintype "passive+no_connect"))
    )
    (net (code "68") (name "unconnected-(U7200-NC-Pad52)") (class "Default")
      (node (ref "U7200") (pin "52") (pinfunction "NC_52") (pintype "passive+no_connect"))
    )
  )
)
